# SCH_towed-rov_2022-07-17.net
KiCad netlist of a schematic drawn in EasyEDA
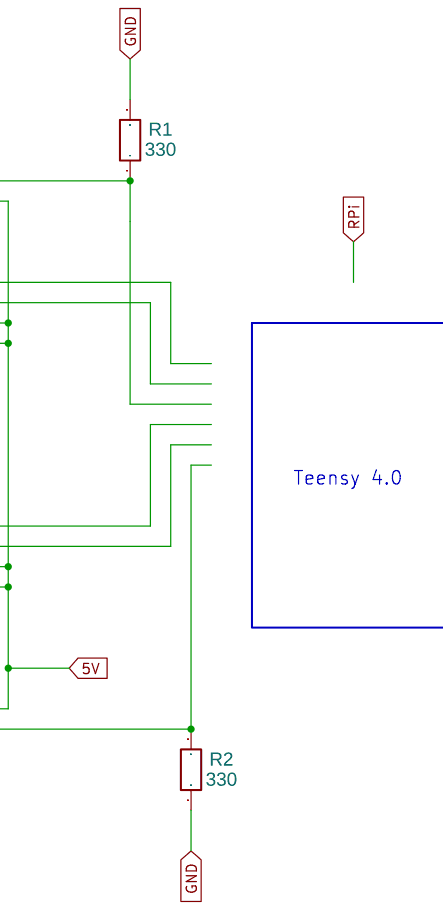
[diagram p0: schematic sheet]

(export (version "E")
  (design (tool "Eeschema 10.0.6"))
  (components
    (comp (ref "R1") (value "330") (libsource (lib "") (part "R_0603_EU")))
    (comp (ref "R2") (value "330") (libsource (lib "") (part "R_0603_EU")))
  )
  (nets
    (net (code "3") (name "GND") (class "Default")
      (node (ref "R1") (pin "2") (pinfunction "2_2") (pintype "unspecified"))
      (node (ref "R2") (pin "1") (pinfunction "1_1") (pintype "unspecified"))
    )
    (net (code "5") (name "unconnected-(R1-Pad1)") (class "Default")
      (node (ref "R1") (pin "1") (pinfunction "1_1") (pintype "unspecified"))
    )
    (net (code "6") (name "unconnected-(R2-Pad2)") (class "Default")
      (node (ref "R2") (pin "2") (pinfunction "2_2") (pintype "unspecified"))
    )
  )
)
